# SDIO_SDcard.net
KiCad netlist of a schematic drawn in Altium Designer
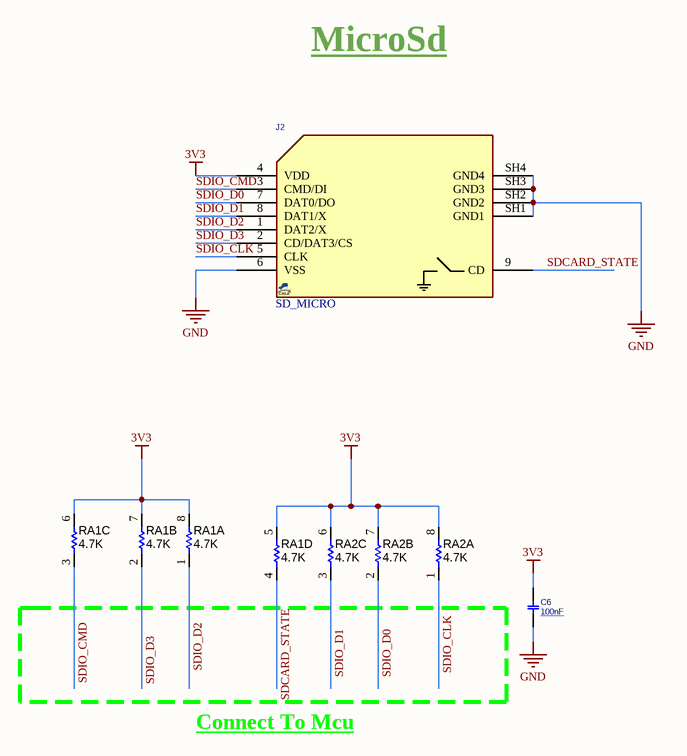
[diagram p0: SDIO_SDcard.SchDoc]

(export (version "E")
  (design (tool "Eeschema 10.0.6"))
  (components
    (comp (ref "C6")
      (value "100nF")
      (footprint "C0603")
      (description "CAP, MLCC, -F, -V, MATERIAL, -%, 0201")
      (fields (field (name "MANF_P#") "MANF_PART#"))
      (libsource (lib "passive_smd") (part "CAP_SMD_MLCC_0603"))
    )
    (comp (ref "J2")
      (value "SD_MICRO")
      (footprint "SDMICRO_AT")
      (description "SD MICRO exist in Iran, Attend 112J-TDAR-R01")
      (fields (field (name "MANF") "Attend") (field (name "MANF_P#") "112J-TDAR-R01"))
      (libsource (lib "socket_card") (part "SOCKET_SDMICRO_AT"))
    )
    (comp (ref "RA1")
      (value "4.7K")
      (footprint "RP0603X4")
      (description "RESISTOR, SMD, PACKX4")
      (fields (field (name "MANF") "MANF") (field (name "MANF_P#") "MANF_PART#"))
      (libsource (lib "passive_smd") (part "RES_SMD_PACK_X4"))
    )
    (comp (ref "RA2")
      (value "4.7K")
      (footprint "RP0603X4")
      (description "RESISTOR, SMD, PACKX4")
      (fields (field (name "MANF") "MANF") (field (name "MANF_P#") "MANF_PART#"))
      (libsource (lib "passive_smd") (part "RES_SMD_PACK_X4"))
    )
  )
  (nets
    (net (code "1") (name "/SDCARD_STATE") (class "Default")
      (node (ref "J2") (pin "9") (pinfunction "CD_9") (pintype "passive"))
      (node (ref "RA1") (pin "4") (pinfunction "4_4") (pintype "passive"))
    )
    (net (code "2") (name "/SDIO_CLK") (class "Default")
      (node (ref "J2") (pin "5") (pinfunction "CLK_5") (pintype "passive"))
      (node (ref "RA2") (pin "1") (pinfunction "1_1") (pintype "passive"))
    )
    (net (code "3") (name "/SDIO_CMD") (class "Default")
      (node (ref "J2") (pin "3") (pinfunction "CMD/DI_3") (pintype "passive"))
      (node (ref "RA1") (pin "3") (pinfunction "3_3") (pintype "passive"))
    )
    (net (code "4") (name "/SDIO_D0") (class "Default")
      (node (ref "J2") (pin "7") (pinfunction "DAT0/DO_7") (pintype "passive"))
      (node (ref "RA2") (pin "2") (pinfunction "2_2") (pintype "passive"))
    )
    (net (code "5") (name "/SDIO_D1") (class "Default")
      (node (ref "J2") (pin "8") (pinfunction "DAT1/X_8") (pintype "passive"))
      (node (ref "RA2") (pin "3") (pinfunction "3_3") (pintype "passive"))
    )
    (net (code "6") (name "/SDIO_D2") (class "Default")
      (node (ref "J2") (pin "1") (pinfunction "DAT2/X_1") (pintype "passive"))
      (node (ref "RA1") (pin "1") (pinfunction "1_1") (pintype "passive"))
    )
    (net (code "7") (name "/SDIO_D3") (class "Default")
      (node (ref "J2") (pin "2") (pinfunction "CD/DAT3/CS_2") (pintype "passive"))
      (node (ref "RA1") (pin "2") (pinfunction "2_2") (pintype "passive"))
    )
    (net (code "8") (name "3V3") (class "Default")
      (node (ref "C6") (pin "2") (pinfunction "2_2") (pintype "passive"))
      (node (ref "J2") (pin "4") (pinfunction "VDD_4") (pintype "passive"))
      (node (ref "RA1") (pin "5") (pinfunction "5_5") (pintype "passive"))
      (node (ref "RA1") (pin "6") (pinfunction "6_6") (pintype "passive"))
      (node (ref "RA1") (pin "7") (pinfunction "7_7") (pintype "passive"))
      (node (ref "RA1") (pin "8") (pinfunction "8_8") (pintype "passive"))
      (node (ref "RA2") (pin "6") (pinfunction "6_6") (pintype "passive"))
      (node (ref "RA2") (pin "7") (pinfunction "7_7") (pintype "passive"))
      (node (ref "RA2") (pin "8") (pinfunction "8_8") (pintype "passive"))
    )
    (net (code "9") (name "GND") (class "Default")
      (node (ref "C6") (pin "1") (pinfunction "1_1") (pintype "passive"))
      (node (ref "J2") (pin "6") (pinfunction "VSS_6") (pintype "passive"))
      (node (ref "J2") (pin "SH1") (pinfunction "GND1_SH1") (pintype "passive"))
      (node (ref "J2") (pin "SH2") (pinfunction "GND2_SH2") (pintype "passive"))
      (node (ref "J2") (pin "SH3") (pinfunction "GND3_SH3") (pintype "passive"))
      (node (ref "J2") (pin "SH4") (pinfunction "GND4_SH4") (pintype "passive"))
    )
  )
)
